# pwm-inverter.net
KiCad netlist of a schematic drawn in EAGLE
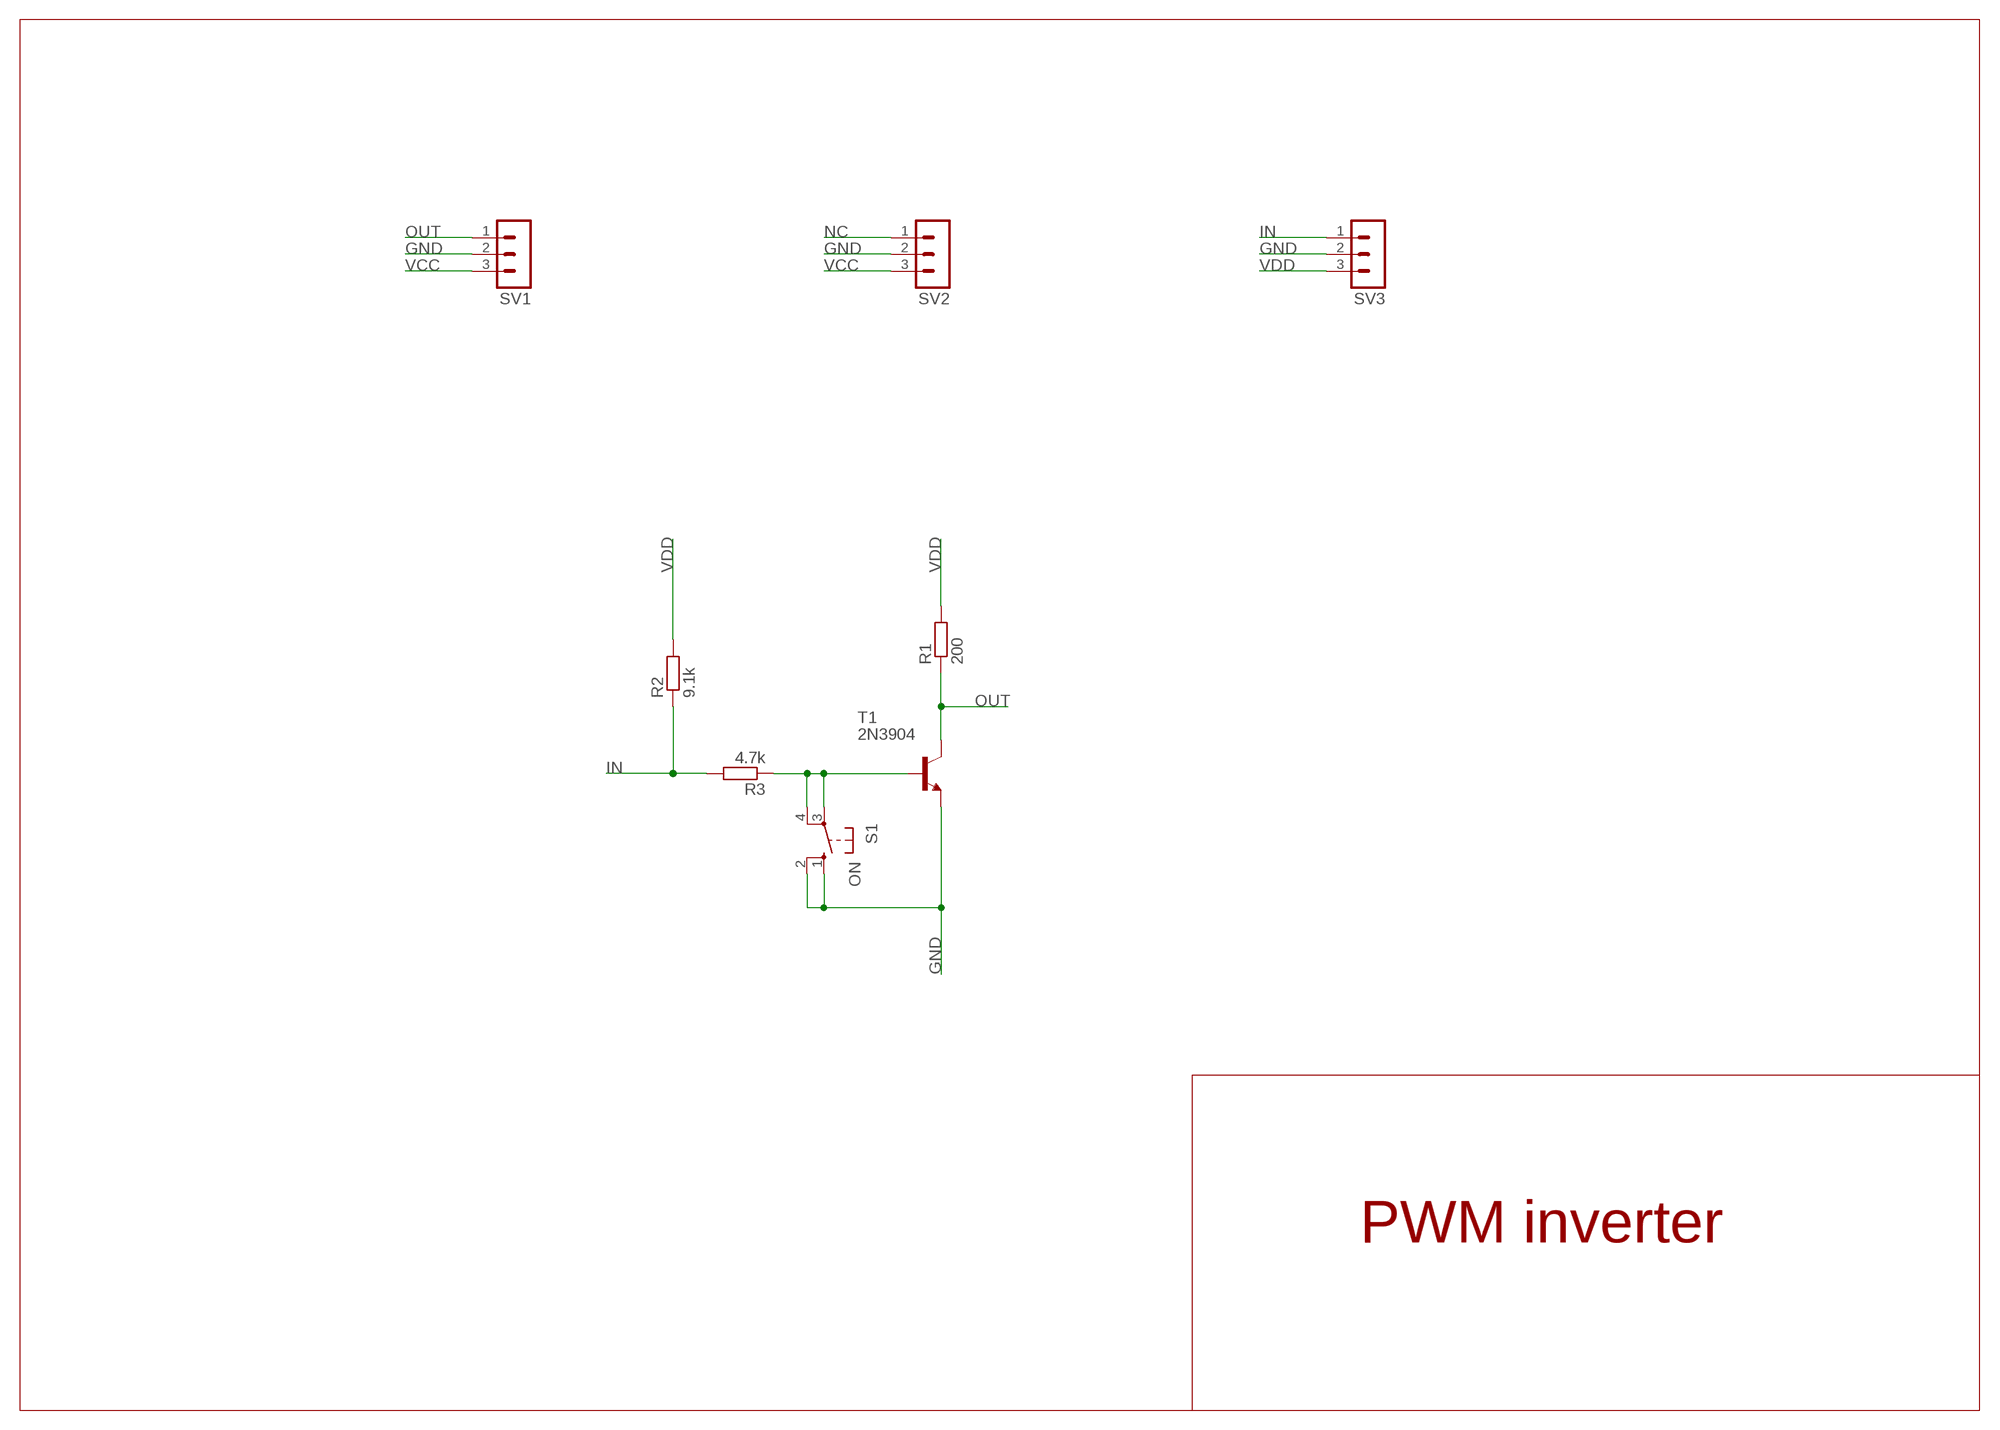
[diagram p0: schematic, sheet 1]
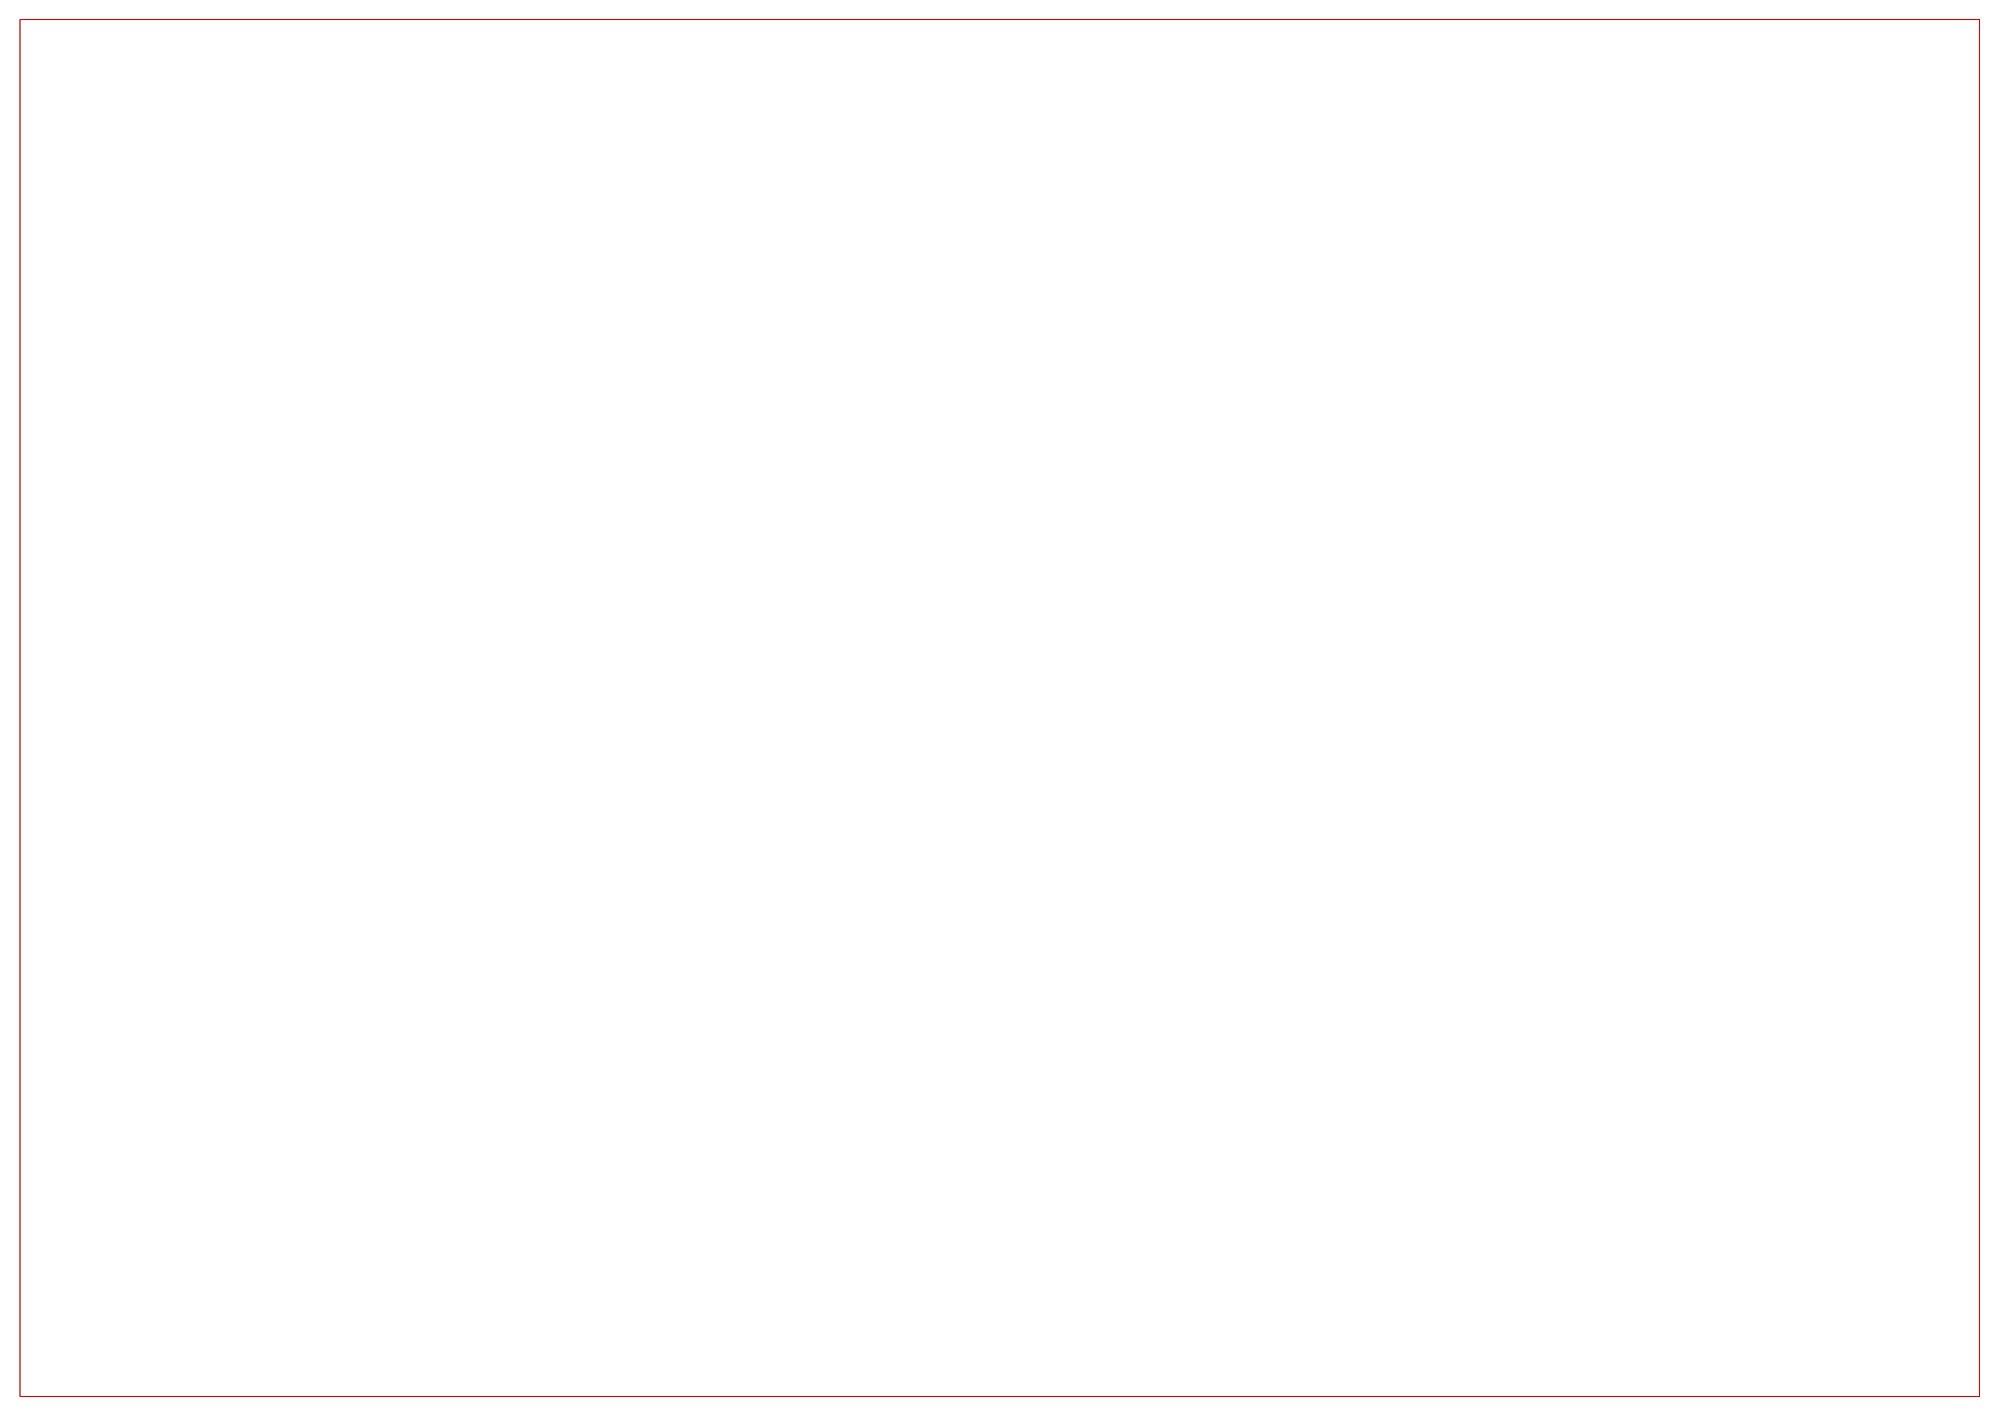
[diagram p1: schematic, sheet 2]

(export (version "E")
  (design (tool "Eeschema 10.0.6"))
  (components
    (comp (ref "R1")
      (value "200")
      (footprint "eagle-import:0207_10")
      (libsource (lib "eagle-import") (part "R-EU_0207/10"))
    )
    (comp (ref "R2")
      (value "9.1k")
      (footprint "eagle-import:0207_10")
      (libsource (lib "eagle-import") (part "R-EU_0207/10"))
    )
    (comp (ref "R3")
      (value "4.7k")
      (footprint "eagle-import:0207_10")
      (libsource (lib "eagle-import") (part "R-EU_0207/10"))
    )
    (comp (ref "S1")
      (value "ON")
      (footprint "eagle-import:B3F-10XX")
      (fields (field (name "MPN") "B3F-1000"))
      (libsource (lib "eagle-import") (part "10-XX"))
    )
    (comp (ref "SV1")
      (value "MA03-1")
      (footprint "eagle-import:MA03-1")
      (libsource (lib "eagle-import") (part "MA03-1"))
    )
    (comp (ref "SV2")
      (value "MA03-1")
      (footprint "eagle-import:MA03-1")
      (libsource (lib "eagle-import") (part "MA03-1"))
    )
    (comp (ref "SV3")
      (value "MA03-1")
      (footprint "eagle-import:MA03-1")
      (libsource (lib "eagle-import") (part "MA03-1"))
    )
    (comp (ref "T1")
      (value "2N3904")
      (footprint "eagle-import:TO92")
      (libsource (lib "eagle-import") (part "2N3904"))
    )
  )
  (nets
    (net (code "1") (name "GND") (class "Default")
      (node (ref "S1") (pin "1") (pinfunction "S_1") (pintype "passive"))
      (node (ref "S1") (pin "2") (pinfunction "S1_2") (pintype "passive"))
      (node (ref "SV1") (pin "2") (pinfunction "2_2") (pintype "passive"))
      (node (ref "SV2") (pin "2") (pinfunction "2_2") (pintype "passive"))
      (node (ref "SV3") (pin "2") (pinfunction "2_2") (pintype "passive"))
      (node (ref "T1") (pin "3") (pinfunction "E_3") (pintype "passive"))
    )
    (net (code "2") (name "IN") (class "Default")
      (node (ref "R2") (pin "1") (pinfunction "1_1") (pintype "passive"))
      (node (ref "R3") (pin "2") (pinfunction "2_2") (pintype "passive"))
      (node (ref "SV3") (pin "1") (pinfunction "1_1") (pintype "passive"))
    )
    (net (code "3") (name "NC") (class "Default")
      (node (ref "SV2") (pin "1") (pinfunction "1_1") (pintype "passive"))
    )
    (net (code "4") (name "Net-(S1-P)") (class "Default")
      (node (ref "R3") (pin "1") (pinfunction "1_1") (pintype "passive"))
      (node (ref "S1") (pin "3") (pinfunction "P_3") (pintype "passive"))
      (node (ref "S1") (pin "4") (pinfunction "P1_4") (pintype "passive"))
      (node (ref "T1") (pin "2") (pinfunction "B_2") (pintype "passive"))
    )
    (net (code "5") (name "OUT") (class "Default")
      (node (ref "R1") (pin "1") (pinfunction "1_1") (pintype "passive"))
      (node (ref "SV1") (pin "1") (pinfunction "1_1") (pintype "passive"))
      (node (ref "T1") (pin "1") (pinfunction "C_1") (pintype "passive"))
    )
    (net (code "6") (name "VCC") (class "Default")
      (node (ref "SV1") (pin "3") (pinfunction "3_3") (pintype "passive"))
      (node (ref "SV2") (pin "3") (pinfunction "3_3") (pintype "passive"))
    )
    (net (code "7") (name "VDD") (class "Default")
      (node (ref "R1") (pin "2") (pinfunction "2_2") (pintype "passive"))
      (node (ref "R2") (pin "2") (pinfunction "2_2") (pintype "passive"))
      (node (ref "SV3") (pin "3") (pinfunction "3_3") (pintype "passive"))
    )
  )
)
